# photodiode-opamp-tester-mk-1_0.net
KiCad netlist of a schematic drawn in EAGLE
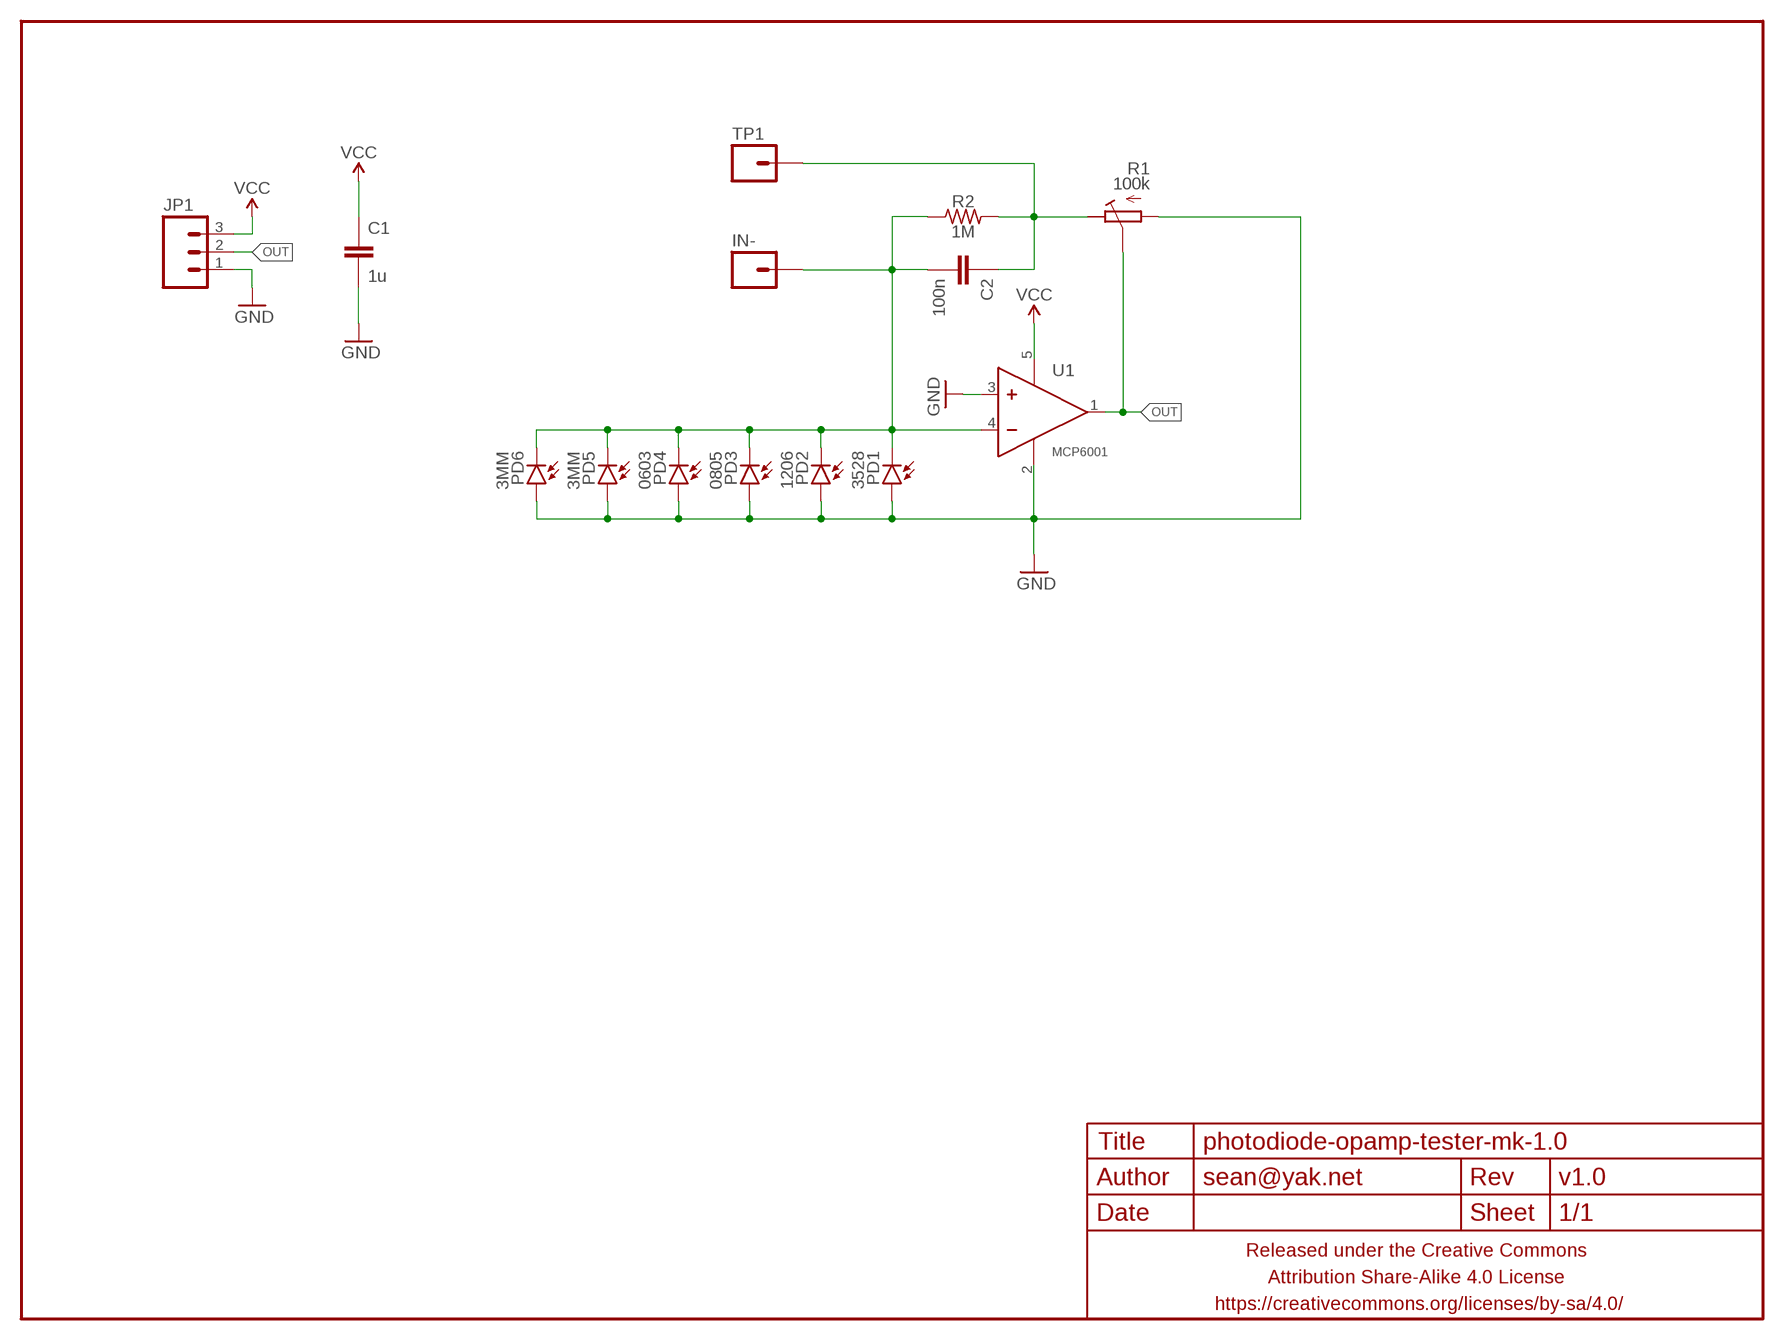
[diagram p0: schematic, sheet 1]

(export (version "E")
  (design (tool "Eeschema 10.0.6"))
  (components
    (comp (ref "C1")
      (value "1u")
      (footprint "eagle-import:C0603")
      (libsource (lib "eagle-import") (part "CAPACITOR-CERAMICC0603"))
    )
    (comp (ref "C2")
      (value "100n")
      (footprint "eagle-import:C0603")
      (libsource (lib "eagle-import") (part "CAPACITOR-CERAMICC0603"))
    )
    (comp (ref "FRAME1")
      (value "FRAME-LETTERNO_PACKAGE")
      (footprint "eagle-import:DUMMY")
      (fields (field (name "DESIGNER") "sean@yak.net") (field (name "VERSION") "v1.0"))
      (libsource (lib "eagle-import") (part "FRAME-LETTERNO_PACKAGE"))
    )
    (comp (ref "IN-")
      (value "M01PTH")
      (footprint "eagle-import:1X01")
      (libsource (lib "eagle-import") (part "M01PTH"))
    )
    (comp (ref "JP1")
      (value "M03PTH-CENTERED")
      (footprint "eagle-import:1X03-CENTERED")
      (libsource (lib "eagle-import") (part "M03PTH-CENTERED"))
    )
    (comp (ref "PD1")
      (value "3528")
      (footprint "eagle-import:LED3528")
      (libsource (lib "eagle-import") (part "PHOTODIODESMD-3528"))
    )
    (comp (ref "PD2")
      (value "1206")
      (footprint "eagle-import:LED-1206")
      (libsource (lib "eagle-import") (part "PHOTODIODESMD-1206"))
    )
    (comp (ref "PD3")
      (value "0805")
      (footprint "eagle-import:LED-0805")
      (libsource (lib "eagle-import") (part "PHOTODIODESMD-0805"))
    )
    (comp (ref "PD4")
      (value "0603")
      (footprint "eagle-import:LED-0603")
      (libsource (lib "eagle-import") (part "PHOTODIODESMD-0603"))
    )
    (comp (ref "PD5")
      (value "3MM")
      (footprint "eagle-import:LED3MM-LESSSILK")
      (libsource (lib "eagle-import") (part "PHOTODIODEPTH-3MM"))
    )
    (comp (ref "PD6")
      (value "3MM")
      (footprint "eagle-import:LED5MM_SHORTPADS")
      (libsource (lib "eagle-import") (part "PHOTODIODEPTH-5MM"))
    )
    (comp (ref "R1")
      (value "100k")
      (footprint "eagle-import:EVM3Y")
      (libsource (lib "eagle-import") (part "POTENTIOMETEREVM3Y"))
    )
    (comp (ref "R2")
      (value "1M")
      (footprint "eagle-import:R0603")
      (libsource (lib "eagle-import") (part "RESISTORR0603"))
    )
    (comp (ref "TP1")
      (value "M01PTH")
      (footprint "eagle-import:1X01")
      (libsource (lib "eagle-import") (part "M01PTH"))
    )
    (comp (ref "U1")
      (value "MCP6001")
      (footprint "eagle-import:SOT23-5")
      (libsource (lib "eagle-import") (part "MCP6001SOT23-5"))
    )
  )
  (nets
    (net (code "1") (name "GND") (class "Default")
      (node (ref "C1") (pin "2") (pinfunction "2_2") (pintype "passive"))
      (node (ref "JP1") (pin "1") (pinfunction "1_1") (pintype "passive"))
      (node (ref "PD1") (pin "A") (pinfunction "A_A") (pintype "passive"))
      (node (ref "PD2") (pin "A") (pinfunction "A_A") (pintype "passive"))
      (node (ref "PD3") (pin "A") (pinfunction "A_A") (pintype "passive"))
      (node (ref "PD4") (pin "A") (pinfunction "A_A") (pintype "passive"))
      (node (ref "PD5") (pin "A") (pinfunction "A_A") (pintype "passive"))
      (node (ref "PD6") (pin "A") (pinfunction "A_A") (pintype "passive"))
      (node (ref "R1") (pin "A") (pinfunction "A_A") (pintype "passive"))
      (node (ref "U1") (pin "2") (pinfunction "V-_2") (pintype "power_in"))
      (node (ref "U1") (pin "3") (pinfunction "IN+_3") (pintype "input"))
    )
    (net (code "2") (name "Net-(C2-Pad1)") (class "Default")
      (node (ref "C2") (pin "1") (pinfunction "1_1") (pintype "passive"))
      (node (ref "R1") (pin "E") (pinfunction "E_E") (pintype "passive"))
      (node (ref "R2") (pin "2") (pinfunction "2_2") (pintype "passive"))
      (node (ref "TP1") (pin "1") (pinfunction "1_1") (pintype "passive"))
    )
    (net (code "3") (name "Net-(PD1-C)") (class "Default")
      (node (ref "C2") (pin "2") (pinfunction "2_2") (pintype "passive"))
      (node (ref "IN-") (pin "1") (pinfunction "1_1") (pintype "passive"))
      (node (ref "PD1") (pin "K") (pinfunction "C_K") (pintype "passive"))
      (node (ref "PD2") (pin "C") (pinfunction "C_C") (pintype "passive"))
      (node (ref "PD3") (pin "C") (pinfunction "C_C") (pintype "passive"))
      (node (ref "PD4") (pin "C") (pinfunction "C_C") (pintype "passive"))
      (node (ref "PD5") (pin "K") (pinfunction "C_K") (pintype "passive"))
      (node (ref "PD6") (pin "K") (pinfunction "C_K") (pintype "passive"))
      (node (ref "R2") (pin "1") (pinfunction "1_1") (pintype "passive"))
      (node (ref "U1") (pin "4") (pinfunction "IN-_4") (pintype "input"))
    )
    (net (code "4") (name "OUT") (class "Default")
      (node (ref "JP1") (pin "2") (pinfunction "2_2") (pintype "passive"))
      (node (ref "R1") (pin "S") (pinfunction "S_S") (pintype "passive"))
      (node (ref "U1") (pin "1") (pinfunction "OUT_1") (pintype "output"))
    )
    (net (code "5") (name "VCC") (class "Default")
      (node (ref "C1") (pin "1") (pinfunction "1_1") (pintype "passive"))
      (node (ref "JP1") (pin "3") (pinfunction "3_3") (pintype "passive"))
      (node (ref "U1") (pin "5") (pinfunction "V+_5") (pintype "power_in"))
    )
  )
)
